# LC_LPF_T.net
KiCad netlist of a schematic drawn in Altium Designer
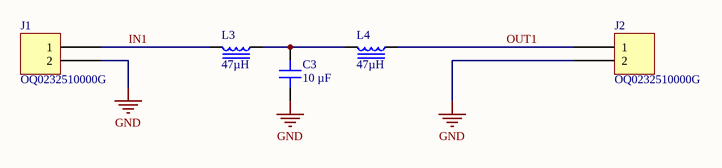
[diagram p0: LC_LPF_T.SchDoc]

(export (version "E")
  (design (tool "Eeschema 10.0.6"))
  (components
    (comp (ref "C3")
      (value "10 µF")
      (footprint "CAP 0603_1608")
      (description "CAP CER 10UF 10V X5R 0603")
      (fields
        (field (name "PART NUMBER") "MD0603BW106M100NHT-EM")
        (field (name "MANUFACTURER") "Knowles Novacap")
      )
      (libsource (lib "Celestial Altium Library - altium_library") (part "Capacitor"))
    )
    (comp (ref "J1")
      (value "OQ0232510000G")
      (footprint "FCI 06-381-2PIN")
      (description "TERM BLOCK HDR 2POS 90DEG 3.81MM")
      (fields (field (name "MANUFACTURER") "Amphenol Anytek"))
      (libsource (lib "") (part "2 Pin_1"))
    )
    (comp (ref "J2")
      (value "OQ0232510000G")
      (footprint "FCI 06-381-2PIN")
      (description "TERM BLOCK HDR 2POS 90DEG 3.81MM")
      (fields (field (name "MANUFACTURER") "Amphenol Anytek"))
      (libsource (lib "Celestial Altium Library - altium_library") (part "2 Pin"))
    )
    (comp (ref "L3")
      (value "47µH")
      (footprint "IND 0603_1608 RF WW")
      (description "INDUCTORPOWER LINE 0603 47H 20%")
      (fields (field (name "PART NUMBER") "L0603B470MPWFT") (field (name "MANUFACTURER") "KEMET"))
      (libsource (lib "Celestial Altium Library - altium_library") (part "Inductor"))
    )
    (comp (ref "L4")
      (value "47µH")
      (footprint "IND 0603_1608 RF WW")
      (description "INDUCTORPOWER LINE 0603 47H 20%")
      (fields (field (name "PART NUMBER") "L0603B470MPWFT") (field (name "MANUFACTURER") "KEMET"))
      (libsource (lib "Celestial Altium Library - altium_library") (part "Inductor"))
    )
  )
  (nets
    (net (code "1") (name "/IN1") (class "Default")
      (node (ref "J1") (pin "1") (pinfunction "1_1") (pintype "passive"))
      (node (ref "L3") (pin "2") (pinfunction "2_2") (pintype "passive"))
    )
    (net (code "2") (name "/OUT1") (class "Default")
      (node (ref "J2") (pin "1") (pinfunction "1_1") (pintype "passive"))
      (node (ref "L4") (pin "1") (pinfunction "1_1") (pintype "passive"))
    )
    (net (code "3") (name "GND") (class "Default")
      (node (ref "C3") (pin "1") (pinfunction "1_1") (pintype "passive"))
      (node (ref "J1") (pin "2") (pinfunction "2_2") (pintype "passive"))
      (node (ref "J2") (pin "2") (pinfunction "2_2") (pintype "passive"))
    )
    (net (code "4") (name "Net-(C3-Pad2)") (class "Default")
      (node (ref "C3") (pin "2") (pinfunction "2_2") (pintype "passive"))
      (node (ref "L3") (pin "1") (pinfunction "1_1") (pintype "passive"))
      (node (ref "L4") (pin "2") (pinfunction "2_2") (pintype "passive"))
    )
  )
)
